# Output.net
KiCad netlist of a schematic drawn in Altium Designer
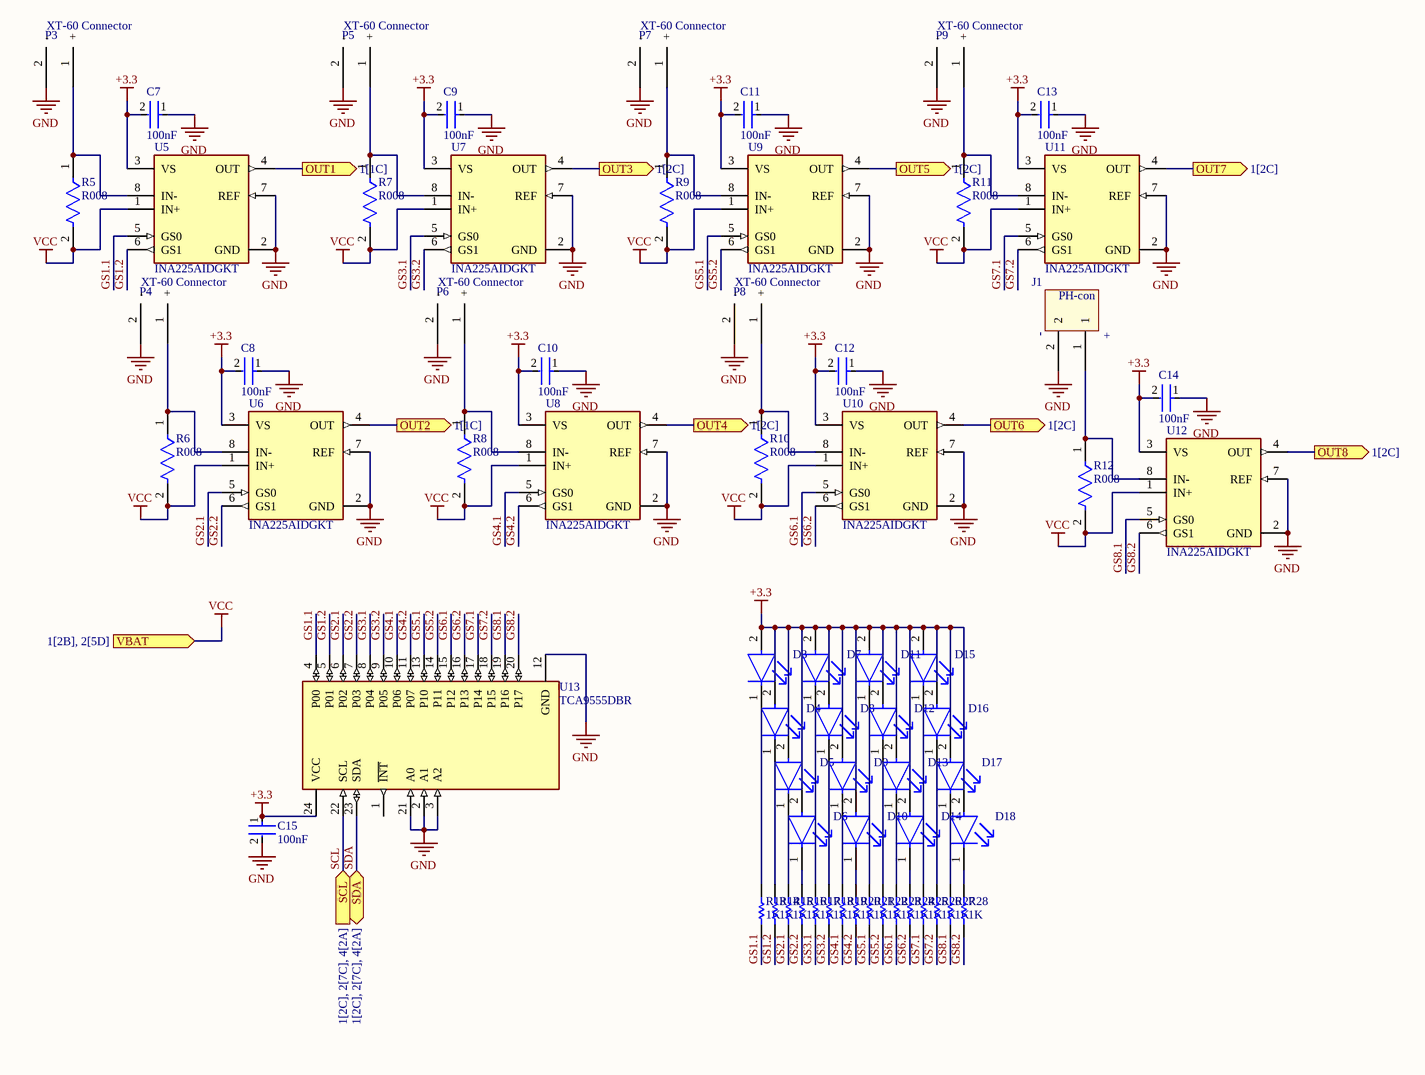
[diagram p0: Output.SchDoc]

(export (version "E")
  (design (tool "Eeschema 10.0.6"))
  (components
    (comp (ref "C7")
      (value "100nF")
      (footprint "FP-0805-L_2_01_0_2-W_1_25-IPC_B")
      (description "General Purpose Ceramic Capacitor, 0805, 100nF, 10%, X7R, 15%, 100V")
      (fields (field (name "VOLTAGE") "100V") (field (name "TOLERANCE") "10%"))
      (libsource (lib "Altium Content Vault") (part "b4654b650e69147ec39a6b967a45e02"))
    )
    (comp (ref "C8")
      (value "100nF")
      (footprint "FP-0805-L_2_01_0_2-W_1_25-IPC_B")
      (description "General Purpose Ceramic Capacitor, 0805, 100nF, 10%, X7R, 15%, 100V")
      (fields (field (name "VOLTAGE") "100V") (field (name "TOLERANCE") "10%"))
      (libsource (lib "Altium Content Vault") (part "b4654b650e69147ec39a6b967a45e02"))
    )
    (comp (ref "C9")
      (value "100nF")
      (footprint "FP-0805-L_2_01_0_2-W_1_25-IPC_B")
      (description "General Purpose Ceramic Capacitor, 0805, 100nF, 10%, X7R, 15%, 100V")
      (fields (field (name "VOLTAGE") "100V") (field (name "TOLERANCE") "10%"))
      (libsource (lib "Altium Content Vault") (part "b4654b650e69147ec39a6b967a45e02"))
    )
    (comp (ref "C10")
      (value "100nF")
      (footprint "FP-0805-L_2_01_0_2-W_1_25-IPC_B")
      (description "General Purpose Ceramic Capacitor, 0805, 100nF, 10%, X7R, 15%, 100V")
      (fields (field (name "VOLTAGE") "100V") (field (name "TOLERANCE") "10%"))
      (libsource (lib "Altium Content Vault") (part "b4654b650e69147ec39a6b967a45e02"))
    )
    (comp (ref "C11")
      (value "100nF")
      (footprint "FP-0805-L_2_01_0_2-W_1_25-IPC_B")
      (description "General Purpose Ceramic Capacitor, 0805, 100nF, 10%, X7R, 15%, 100V")
      (fields (field (name "VOLTAGE") "100V") (field (name "TOLERANCE") "10%"))
      (libsource (lib "Altium Content Vault") (part "b4654b650e69147ec39a6b967a45e02"))
    )
    (comp (ref "C12")
      (value "100nF")
      (footprint "FP-0805-L_2_01_0_2-W_1_25-IPC_B")
      (description "General Purpose Ceramic Capacitor, 0805, 100nF, 10%, X7R, 15%, 100V")
      (fields (field (name "VOLTAGE") "100V") (field (name "TOLERANCE") "10%"))
      (libsource (lib "Altium Content Vault") (part "b4654b650e69147ec39a6b967a45e02"))
    )
    (comp (ref "C13")
      (value "100nF")
      (footprint "FP-0805-L_2_01_0_2-W_1_25-IPC_B")
      (description "General Purpose Ceramic Capacitor, 0805, 100nF, 10%, X7R, 15%, 100V")
      (fields (field (name "VOLTAGE") "100V") (field (name "TOLERANCE") "10%"))
      (libsource (lib "Altium Content Vault") (part "b4654b650e69147ec39a6b967a45e02"))
    )
    (comp (ref "C14")
      (value "100nF")
      (footprint "FP-0805-L_2_01_0_2-W_1_25-IPC_B")
      (description "General Purpose Ceramic Capacitor, 0805, 100nF, 10%, X7R, 15%, 100V")
      (fields (field (name "VOLTAGE") "100V") (field (name "TOLERANCE") "10%"))
      (libsource (lib "Altium Content Vault") (part "b4654b650e69147ec39a6b967a45e02"))
    )
    (comp (ref "C15")
      (value "100nF")
      (footprint "FP-0805-L_2_01_0_2-W_1_25-IPC_B")
      (description "General Purpose Ceramic Capacitor, 0805, 100nF, 10%, X7R, 15%, 100V")
      (fields (field (name "VOLTAGE") "100V") (field (name "TOLERANCE") "10%"))
      (libsource (lib "Altium Content Vault") (part "b4654b650e69147ec39a6b967a45e02"))
    )
    (comp (ref "D3")
      (value "TLLG4401")
      (footprint "FP-6_544-5255_01-4-MFG")
      (description "TLLG4401 LED, Green, 2mcd, 3mmDia., T-1, +/-25deg, 565nm, 7mA, 1.9V Vf, 20V Vr, 20mW, -40")
      (libsource (lib "Altium Content Vault") (part "8706943c75ba83719d021d2fdc84c58"))
    )
    (comp (ref "D4")
      (value "TLLG4401")
      (footprint "FP-6_544-5255_01-4-MFG")
      (description "TLLG4401 LED, Green, 2mcd, 3mmDia., T-1, +/-25deg, 565nm, 7mA, 1.9V Vf, 20V Vr, 20mW, -40")
      (libsource (lib "Altium Content Vault") (part "8706943c75ba83719d021d2fdc84c58"))
    )
    (comp (ref "D5")
      (value "TLLG4401")
      (footprint "FP-6_544-5255_01-4-MFG")
      (description "TLLG4401 LED, Green, 2mcd, 3mmDia., T-1, +/-25deg, 565nm, 7mA, 1.9V Vf, 20V Vr, 20mW, -40")
      (libsource (lib "Altium Content Vault") (part "8706943c75ba83719d021d2fdc84c58"))
    )
    (comp (ref "D6")
      (value "TLLG4401")
      (footprint "FP-6_544-5255_01-4-MFG")
      (description "TLLG4401 LED, Green, 2mcd, 3mmDia., T-1, +/-25deg, 565nm, 7mA, 1.9V Vf, 20V Vr, 20mW, -40")
      (libsource (lib "Altium Content Vault") (part "8706943c75ba83719d021d2fdc84c58"))
    )
    (comp (ref "D7")
      (value "TLLG4401")
      (footprint "FP-6_544-5255_01-4-MFG")
      (description "TLLG4401 LED, Green, 2mcd, 3mmDia., T-1, +/-25deg, 565nm, 7mA, 1.9V Vf, 20V Vr, 20mW, -40")
      (libsource (lib "Altium Content Vault") (part "8706943c75ba83719d021d2fdc84c58"))
    )
    (comp (ref "D8")
      (value "TLLG4401")
      (footprint "FP-6_544-5255_01-4-MFG")
      (description "TLLG4401 LED, Green, 2mcd, 3mmDia., T-1, +/-25deg, 565nm, 7mA, 1.9V Vf, 20V Vr, 20mW, -40")
      (libsource (lib "Altium Content Vault") (part "8706943c75ba83719d021d2fdc84c58"))
    )
    (comp (ref "D9")
      (value "TLLG4401")
      (footprint "FP-6_544-5255_01-4-MFG")
      (description "TLLG4401 LED, Green, 2mcd, 3mmDia., T-1, +/-25deg, 565nm, 7mA, 1.9V Vf, 20V Vr, 20mW, -40")
      (libsource (lib "Altium Content Vault") (part "8706943c75ba83719d021d2fdc84c58"))
    )
    (comp (ref "D10")
      (value "TLLG4401")
      (footprint "FP-6_544-5255_01-4-MFG")
      (description "TLLG4401 LED, Green, 2mcd, 3mmDia., T-1, +/-25deg, 565nm, 7mA, 1.9V Vf, 20V Vr, 20mW, -40")
      (libsource (lib "Altium Content Vault") (part "8706943c75ba83719d021d2fdc84c58"))
    )
    (comp (ref "D11")
      (value "TLLG4401")
      (footprint "FP-6_544-5255_01-4-MFG")
      (description "TLLG4401 LED, Green, 2mcd, 3mmDia., T-1, +/-25deg, 565nm, 7mA, 1.9V Vf, 20V Vr, 20mW, -40")
      (libsource (lib "Altium Content Vault") (part "8706943c75ba83719d021d2fdc84c58"))
    )
    (comp (ref "D12")
      (value "TLLG4401")
      (footprint "FP-6_544-5255_01-4-MFG")
      (description "TLLG4401 LED, Green, 2mcd, 3mmDia., T-1, +/-25deg, 565nm, 7mA, 1.9V Vf, 20V Vr, 20mW, -40")
      (libsource (lib "Altium Content Vault") (part "8706943c75ba83719d021d2fdc84c58"))
    )
    (comp (ref "D13")
      (value "TLLG4401")
      (footprint "FP-6_544-5255_01-4-MFG")
      (description "TLLG4401 LED, Green, 2mcd, 3mmDia., T-1, +/-25deg, 565nm, 7mA, 1.9V Vf, 20V Vr, 20mW, -40")
      (libsource (lib "Altium Content Vault") (part "8706943c75ba83719d021d2fdc84c58"))
    )
    (comp (ref "D14")
      (value "TLLG4401")
      (footprint "FP-6_544-5255_01-4-MFG")
      (description "TLLG4401 LED, Green, 2mcd, 3mmDia., T-1, +/-25deg, 565nm, 7mA, 1.9V Vf, 20V Vr, 20mW, -40")
      (libsource (lib "Altium Content Vault") (part "8706943c75ba83719d021d2fdc84c58"))
    )
    (comp (ref "D15")
      (value "TLLG4401")
      (footprint "FP-6_544-5255_01-4-MFG")
      (description "TLLG4401 LED, Green, 2mcd, 3mmDia., T-1, +/-25deg, 565nm, 7mA, 1.9V Vf, 20V Vr, 20mW, -40")
      (libsource (lib "Altium Content Vault") (part "8706943c75ba83719d021d2fdc84c58"))
    )
    (comp (ref "D16")
      (value "TLLG4401")
      (footprint "FP-6_544-5255_01-4-MFG")
      (description "TLLG4401 LED, Green, 2mcd, 3mmDia., T-1, +/-25deg, 565nm, 7mA, 1.9V Vf, 20V Vr, 20mW, -40")
      (libsource (lib "Altium Content Vault") (part "8706943c75ba83719d021d2fdc84c58"))
    )
    (comp (ref "D17")
      (value "TLLG4401")
      (footprint "FP-6_544-5255_01-4-MFG")
      (description "TLLG4401 LED, Green, 2mcd, 3mmDia., T-1, +/-25deg, 565nm, 7mA, 1.9V Vf, 20V Vr, 20mW, -40")
      (libsource (lib "Altium Content Vault") (part "8706943c75ba83719d021d2fdc84c58"))
    )
    (comp (ref "D18")
      (value "TLLG4401")
      (footprint "FP-6_544-5255_01-4-MFG")
      (description "TLLG4401 LED, Green, 2mcd, 3mmDia., T-1, +/-25deg, 565nm, 7mA, 1.9V Vf, 20V Vr, 20mW, -40")
      (libsource (lib "Altium Content Vault") (part "8706943c75ba83719d021d2fdc84c58"))
    )
    (comp (ref "J1")
      (value "PH-con")
      (footprint "Phoenix")
      (libsource (lib "XT+PHOENIX") (part "Connector_2"))
    )
    (comp (ref "P3")
      (value "XT-60 Connector")
      (footprint "2")
      (fields
        (field (name "MANUFACTURER") "POLOLU")
        (field (name "MANUFACTURER PART NUMBER") "XT60 YELLOW")
        (field (name "SUPPLIER PART NUMBER 1") "XT-60 Connector")
      )
      (libsource (lib "AltiumLibraryDDT") (part "XT-60 Connector"))
    )
    (comp (ref "P4")
      (value "XT-60 Connector")
      (footprint "2")
      (fields
        (field (name "MANUFACTURER") "POLOLU")
        (field (name "MANUFACTURER PART NUMBER") "XT60 YELLOW")
        (field (name "SUPPLIER PART NUMBER 1") "XT-60 Connector")
      )
      (libsource (lib "AltiumLibraryDDT") (part "XT-60 Connector"))
    )
    (comp (ref "P5")
      (value "XT-60 Connector")
      (footprint "2")
      (fields
        (field (name "MANUFACTURER") "POLOLU")
        (field (name "MANUFACTURER PART NUMBER") "XT60 YELLOW")
        (field (name "SUPPLIER PART NUMBER 1") "XT-60 Connector")
      )
      (libsource (lib "AltiumLibraryDDT") (part "XT-60 Connector"))
    )
    (comp (ref "P6")
      (value "XT-60 Connector")
      (footprint "2")
      (fields
        (field (name "MANUFACTURER") "POLOLU")
        (field (name "MANUFACTURER PART NUMBER") "XT60 YELLOW")
        (field (name "SUPPLIER PART NUMBER 1") "XT-60 Connector")
      )
      (libsource (lib "AltiumLibraryDDT") (part "XT-60 Connector"))
    )
    (comp (ref "P7")
      (value "XT-60 Connector")
      (footprint "2")
      (fields
        (field (name "MANUFACTURER") "POLOLU")
        (field (name "MANUFACTURER PART NUMBER") "XT60 YELLOW")
        (field (name "SUPPLIER PART NUMBER 1") "XT-60 Connector")
      )
      (libsource (lib "AltiumLibraryDDT") (part "XT-60 Connector"))
    )
    (comp (ref "P8")
      (value "XT-60 Connector")
      (footprint "2")
      (fields
        (field (name "MANUFACTURER") "POLOLU")
        (field (name "MANUFACTURER PART NUMBER") "XT60 YELLOW")
        (field (name "SUPPLIER PART NUMBER 1") "XT-60 Connector")
      )
      (libsource (lib "AltiumLibraryDDT") (part "XT-60 Connector"))
    )
    (comp (ref "P9")
      (value "XT-60 Connector")
      (footprint "2")
      (fields
        (field (name "MANUFACTURER") "POLOLU")
        (field (name "MANUFACTURER PART NUMBER") "XT60 YELLOW")
        (field (name "SUPPLIER PART NUMBER 1") "XT-60 Connector")
      )
      (libsource (lib "AltiumLibraryDDT") (part "XT-60 Connector"))
    )
    (comp (ref "R5")
      (value "R008")
      (footprint "FP-RL2512-MFG")
      (description "RES 0.1 OHM 1% 1W 2512")
      (fields
        (field (name "OCTOPART") "https://octopart.com/rl2512fk-070r1l-yageo-42334369")
        (field (name "MANUFACTURER") "YAGEO")
      )
      (libsource (lib "Altium Content Vault") (part "1029c3af85768c4190bb7ad29bc67b5"))
    )
    (comp (ref "R6")
      (value "R008")
      (footprint "FP-RL2512-MFG")
      (description "RES 0.1 OHM 1% 1W 2512")
      (fields
        (field (name "OCTOPART") "https://octopart.com/rl2512fk-070r1l-yageo-42334369")
        (field (name "MANUFACTURER") "YAGEO")
      )
      (libsource (lib "Altium Content Vault") (part "1029c3af85768c4190bb7ad29bc67b5"))
    )
    (comp (ref "R7")
      (value "R008")
      (footprint "FP-RL2512-MFG")
      (description "RES 0.1 OHM 1% 1W 2512")
      (fields
        (field (name "OCTOPART") "https://octopart.com/rl2512fk-070r1l-yageo-42334369")
        (field (name "MANUFACTURER") "YAGEO")
      )
      (libsource (lib "Altium Content Vault") (part "1029c3af85768c4190bb7ad29bc67b5"))
    )
    (comp (ref "R8")
      (value "R008")
      (footprint "FP-RL2512-MFG")
      (description "RES 0.1 OHM 1% 1W 2512")
      (fields
        (field (name "OCTOPART") "https://octopart.com/rl2512fk-070r1l-yageo-42334369")
        (field (name "MANUFACTURER") "YAGEO")
      )
      (libsource (lib "Altium Content Vault") (part "1029c3af85768c4190bb7ad29bc67b5"))
    )
    (comp (ref "R9")
      (value "R008")
      (footprint "FP-RL2512-MFG")
      (description "RES 0.1 OHM 1% 1W 2512")
      (fields
        (field (name "OCTOPART") "https://octopart.com/rl2512fk-070r1l-yageo-42334369")
        (field (name "MANUFACTURER") "YAGEO")
      )
      (libsource (lib "Altium Content Vault") (part "1029c3af85768c4190bb7ad29bc67b5"))
    )
    (comp (ref "R10")
      (value "R008")
      (footprint "FP-RL2512-MFG")
      (description "RES 0.1 OHM 1% 1W 2512")
      (fields
        (field (name "OCTOPART") "https://octopart.com/rl2512fk-070r1l-yageo-42334369")
        (field (name "MANUFACTURER") "YAGEO")
      )
      (libsource (lib "Altium Content Vault") (part "1029c3af85768c4190bb7ad29bc67b5"))
    )
    (comp (ref "R11")
      (value "R008")
      (footprint "FP-RL2512-MFG")
      (description "RES 0.1 OHM 1% 1W 2512")
      (fields
        (field (name "OCTOPART") "https://octopart.com/rl2512fk-070r1l-yageo-42334369")
        (field (name "MANUFACTURER") "YAGEO")
      )
      (libsource (lib "Altium Content Vault") (part "1029c3af85768c4190bb7ad29bc67b5"))
    )
    (comp (ref "R12")
      (value "R008")
      (footprint "FP-RL2512-MFG")
      (description "RES 0.1 OHM 1% 1W 2512")
      (fields
        (field (name "OCTOPART") "https://octopart.com/rl2512fk-070r1l-yageo-42334369")
        (field (name "MANUFACTURER") "YAGEO")
      )
      (libsource (lib "Altium Content Vault") (part "1029c3af85768c4190bb7ad29bc67b5"))
    )
    (comp (ref "R13")
      (value "1K")
      (footprint "RESC2013X60X35ML10T20")
      (description "Chip Resistor, 1 KOhm, +/- 1%, 125 mW, -55 to 155 degC, 0805 (2012 Metric), RoHS, Tape and Reel")
      (fields (field (name "TOLERANCE") "1%") (field (name "MANUFACTURER") "Yageo"))
      (libsource (lib "Altium Content Vault") (part "RES-2"))
    )
    (comp (ref "R14")
      (value "1K")
      (footprint "RESC2013X60X35ML10T20")
      (description "Chip Resistor, 1 KOhm, +/- 1%, 125 mW, -55 to 155 degC, 0805 (2012 Metric), RoHS, Tape and Reel")
      (fields (field (name "TOLERANCE") "1%") (field (name "MANUFACTURER") "Yageo"))
      (libsource (lib "Altium Content Vault") (part "RES-2"))
    )
    (comp (ref "R15")
      (value "1K")
      (footprint "RESC2013X60X35ML10T20")
      (description "Chip Resistor, 1 KOhm, +/- 1%, 125 mW, -55 to 155 degC, 0805 (2012 Metric), RoHS, Tape and Reel")
      (fields (field (name "TOLERANCE") "1%") (field (name "MANUFACTURER") "Yageo"))
      (libsource (lib "Altium Content Vault") (part "RES-2"))
    )
    (comp (ref "R16")
      (value "1K")
      (footprint "RESC2013X60X35ML10T20")
      (description "Chip Resistor, 1 KOhm, +/- 1%, 125 mW, -55 to 155 degC, 0805 (2012 Metric), RoHS, Tape and Reel")
      (fields (field (name "TOLERANCE") "1%") (field (name "MANUFACTURER") "Yageo"))
      (libsource (lib "Altium Content Vault") (part "RES-2"))
    )
    (comp (ref "R17")
      (value "1K")
      (footprint "RESC2013X60X35ML10T20")
      (description "Chip Resistor, 1 KOhm, +/- 1%, 125 mW, -55 to 155 degC, 0805 (2012 Metric), RoHS, Tape and Reel")
      (fields (field (name "TOLERANCE") "1%") (field (name "MANUFACTURER") "Yageo"))
      (libsource (lib "Altium Content Vault") (part "RES-2"))
    )
    (comp (ref "R18")
      (value "1K")
      (footprint "RESC2013X60X35ML10T20")
      (description "Chip Resistor, 1 KOhm, +/- 1%, 125 mW, -55 to 155 degC, 0805 (2012 Metric), RoHS, Tape and Reel")
      (fields (field (name "TOLERANCE") "1%") (field (name "MANUFACTURER") "Yageo"))
      (libsource (lib "Altium Content Vault") (part "RES-2"))
    )
    (comp (ref "R19")
      (value "1K")
      (footprint "RESC2013X60X35ML10T20")
      (description "Chip Resistor, 1 KOhm, +/- 1%, 125 mW, -55 to 155 degC, 0805 (2012 Metric), RoHS, Tape and Reel")
      (fields (field (name "TOLERANCE") "1%") (field (name "MANUFACTURER") "Yageo"))
      (libsource (lib "Altium Content Vault") (part "RES-2"))
    )
    (comp (ref "R20")
      (value "1K")
      (footprint "RESC2013X60X35ML10T20")
      (description "Chip Resistor, 1 KOhm, +/- 1%, 125 mW, -55 to 155 degC, 0805 (2012 Metric), RoHS, Tape and Reel")
      (fields (field (name "TOLERANCE") "1%") (field (name "MANUFACTURER") "Yageo"))
      (libsource (lib "Altium Content Vault") (part "RES-2"))
    )
    (comp (ref "R21")
      (value "1K")
      (footprint "RESC2013X60X35ML10T20")
      (description "Chip Resistor, 1 KOhm, +/- 1%, 125 mW, -55 to 155 degC, 0805 (2012 Metric), RoHS, Tape and Reel")
      (fields (field (name "TOLERANCE") "1%") (field (name "MANUFACTURER") "Yageo"))
      (libsource (lib "Altium Content Vault") (part "RES-2"))
    )
    (comp (ref "R22")
      (value "1K")
      (footprint "RESC2013X60X35ML10T20")
      (description "Chip Resistor, 1 KOhm, +/- 1%, 125 mW, -55 to 155 degC, 0805 (2012 Metric), RoHS, Tape and Reel")
      (fields (field (name "TOLERANCE") "1%") (field (name "MANUFACTURER") "Yageo"))
      (libsource (lib "Altium Content Vault") (part "RES-2"))
    )
    (comp (ref "R23")
      (value "1K")
      (footprint "RESC2013X60X35ML10T20")
      (description "Chip Resistor, 1 KOhm, +/- 1%, 125 mW, -55 to 155 degC, 0805 (2012 Metric), RoHS, Tape and Reel")
      (fields (field (name "TOLERANCE") "1%") (field (name "MANUFACTURER") "Yageo"))
      (libsource (lib "Altium Content Vault") (part "RES-2"))
    )
    (comp (ref "R24")
      (value "1K")
      (footprint "RESC2013X60X35ML10T20")
      (description "Chip Resistor, 1 KOhm, +/- 1%, 125 mW, -55 to 155 degC, 0805 (2012 Metric), RoHS, Tape and Reel")
      (fields (field (name "TOLERANCE") "1%") (field (name "MANUFACTURER") "Yageo"))
      (libsource (lib "Altium Content Vault") (part "RES-2"))
    )
    (comp (ref "R25")
      (value "1K")
      (footprint "RESC2013X60X35ML10T20")
      (description "Chip Resistor, 1 KOhm, +/- 1%, 125 mW, -55 to 155 degC, 0805 (2012 Metric), RoHS, Tape and Reel")
      (fields (field (name "TOLERANCE") "1%") (field (name "MANUFACTURER") "Yageo"))
      (libsource (lib "Altium Content Vault") (part "RES-2"))
    )
    (comp (ref "R26")
      (value "1K")
      (footprint "RESC2013X60X35ML10T20")
      (description "Chip Resistor, 1 KOhm, +/- 1%, 125 mW, -55 to 155 degC, 0805 (2012 Metric), RoHS, Tape and Reel")
      (fields (field (name "TOLERANCE") "1%") (field (name "MANUFACTURER") "Yageo"))
      (libsource (lib "Altium Content Vault") (part "RES-2"))
    )
    (comp (ref "R27")
      (value "1K")
      (footprint "RESC2013X60X35ML10T20")
      (description "Chip Resistor, 1 KOhm, +/- 1%, 125 mW, -55 to 155 degC, 0805 (2012 Metric), RoHS, Tape and Reel")
      (fields (field (name "TOLERANCE") "1%") (field (name "MANUFACTURER") "Yageo"))
      (libsource (lib "Altium Content Vault") (part "RES-2"))
    )
    (comp (ref "R28")
      (value "1K")
      (footprint "RESC2013X60X35ML10T20")
      (description "Chip Resistor, 1 KOhm, +/- 1%, 125 mW, -55 to 155 degC, 0805 (2012 Metric), RoHS, Tape and Reel")
      (fields (field (name "TOLERANCE") "1%") (field (name "MANUFACTURER") "Yageo"))
      (libsource (lib "Altium Content Vault") (part "RES-2"))
    )
    (comp (ref "U5")
      (value "INA225AIDGKT")
      (footprint "FP-INA225AIDGKT-IPC_A")
      (description "IC MONITOR PWR/CUR BIDIR 8VSSOP")
      (fields
        (field (name "OCTOPART") "https://octopart.com/ina225aidgkt-texas+instruments-28946314")
        (field (name "MANUFACTURER") "Texas Instruments")
      )
      (libsource (lib "Altium Content Vault") (part "c359911d667b8e4eb68c8ff16fe5c28"))
    )
    (comp (ref "U6")
      (value "INA225AIDGKT")
      (footprint "FP-INA225AIDGKT-IPC_A")
      (description "IC MONITOR PWR/CUR BIDIR 8VSSOP")
      (fields
        (field (name "OCTOPART") "https://octopart.com/ina225aidgkt-texas+instruments-28946314")
        (field (name "MANUFACTURER") "Texas Instruments")
      )
      (libsource (lib "Altium Content Vault") (part "c359911d667b8e4eb68c8ff16fe5c28"))
    )
    (comp (ref "U7")
      (value "INA225AIDGKT")
      (footprint "FP-INA225AIDGKT-IPC_A")
      (description "IC MONITOR PWR/CUR BIDIR 8VSSOP")
      (fields
        (field (name "OCTOPART") "https://octopart.com/ina225aidgkt-texas+instruments-28946314")
        (field (name "MANUFACTURER") "Texas Instruments")
      )
      (libsource (lib "Altium Content Vault") (part "c359911d667b8e4eb68c8ff16fe5c28"))
    )
    (comp (ref "U8")
      (value "INA225AIDGKT")
      (footprint "FP-INA225AIDGKT-IPC_A")
      (description "IC MONITOR PWR/CUR BIDIR 8VSSOP")
      (fields
        (field (name "OCTOPART") "https://octopart.com/ina225aidgkt-texas+instruments-28946314")
        (field (name "MANUFACTURER") "Texas Instruments")
      )
      (libsource (lib "Altium Content Vault") (part "c359911d667b8e4eb68c8ff16fe5c28"))
    )
    (comp (ref "U9")
      (value "INA225AIDGKT")
      (footprint "FP-INA225AIDGKT-IPC_A")
      (description "IC MONITOR PWR/CUR BIDIR 8VSSOP")
      (fields
        (field (name "OCTOPART") "https://octopart.com/ina225aidgkt-texas+instruments-28946314")
        (field (name "MANUFACTURER") "Texas Instruments")
      )
      (libsource (lib "Altium Content Vault") (part "c359911d667b8e4eb68c8ff16fe5c28"))
    )
    (comp (ref "U10")
      (value "INA225AIDGKT")
      (footprint "FP-INA225AIDGKT-IPC_A")
      (description "IC MONITOR PWR/CUR BIDIR 8VSSOP")
      (fields
        (field (name "OCTOPART") "https://octopart.com/ina225aidgkt-texas+instruments-28946314")
        (field (name "MANUFACTURER") "Texas Instruments")
      )
      (libsource (lib "Altium Content Vault") (part "c359911d667b8e4eb68c8ff16fe5c28"))
    )
    (comp (ref "U11")
      (value "INA225AIDGKT")
      (footprint "FP-INA225AIDGKT-IPC_A")
      (description "IC MONITOR PWR/CUR BIDIR 8VSSOP")
      (fields
        (field (name "OCTOPART") "https://octopart.com/ina225aidgkt-texas+instruments-28946314")
        (field (name "MANUFACTURER") "Texas Instruments")
      )
      (libsource (lib "Altium Content Vault") (part "c359911d667b8e4eb68c8ff16fe5c28"))
    )
    (comp (ref "U12")
      (value "INA225AIDGKT")
      (footprint "FP-INA225AIDGKT-IPC_A")
      (description "IC MONITOR PWR/CUR BIDIR 8VSSOP")
      (fields
        (field (name "OCTOPART") "https://octopart.com/ina225aidgkt-texas+instruments-28946314")
        (field (name "MANUFACTURER") "Texas Instruments")
      )
      (libsource (lib "Altium Content Vault") (part "c359911d667b8e4eb68c8ff16fe5c28"))
    )
    (comp (ref "U13")
      (value "TCA9555DBR")
      (footprint "FP-DB0024A-IPC_A")
      (description "IC I/O EXPANDER 16B 24SSOP")
      (libsource (lib "Altium Content Vault") (part "d0eb17f36d141fc89679fdc1217173a"))
    )
  )
  (nets
    (net (code "1") (name "+3.3") (class "Default")
      (node (ref "C10") (pin "2") (pinfunction "2_2") (pintype "passive"))
      (node (ref "C11") (pin "2") (pinfunction "2_2") (pintype "passive"))
      (node (ref "C12") (pin "2") (pinfunction "2_2") (pintype "passive"))
      (node (ref "C13") (pin "2") (pinfunction "2_2") (pintype "passive"))
      (node (ref "C14") (pin "2") (pinfunction "2_2") (pintype "passive"))
      (node (ref "C15") (pin "1") (pinfunction "1_1") (pintype "passive"))
      (node (ref "C7") (pin "2") (pinfunction "2_2") (pintype "passive"))
      (node (ref "C8") (pin "2") (pinfunction "2_2") (pintype "passive"))
      (node (ref "C9") (pin "2") (pinfunction "2_2") (pintype "passive"))
      (node (ref "D10") (pin "2") (pinfunction "A_2") (pintype "passive"))
      (node (ref "D11") (pin "2") (pinfunction "A_2") (pintype "passive"))
      (node (ref "D12") (pin "2") (pinfunction "A_2") (pintype "passive"))
      (node (ref "D13") (pin "2") (pinfunction "A_2") (pintype "passive"))
      (node (ref "D14") (pin "2") (pinfunction "A_2") (pintype "passive"))
      (node (ref "D15") (pin "2") (pinfunction "A_2") (pintype "passive"))
      (node (ref "D16") (pin "2") (pinfunction "A_2") (pintype "passive"))
      (node (ref "D17") (pin "2") (pinfunction "A_2") (pintype "passive"))
      (node (ref "D18") (pin "2") (pinfunction "A_2") (pintype "passive"))
      (node (ref "D3") (pin "2") (pinfunction "A_2") (pintype "passive"))
      (node (ref "D4") (pin "2") (pinfunction "A_2") (pintype "passive"))
      (node (ref "D5") (pin "2") (pinfunction "A_2") (pintype "passive"))
      (node (ref "D6") (pin "2") (pinfunction "A_2") (pintype "passive"))
      (node (ref "D7") (pin "2") (pinfunction "A_2") (pintype "passive"))
      (node (ref "D8") (pin "2") (pinfunction "A_2") (pintype "passive"))
      (node (ref "D9") (pin "2") (pinfunction "A_2") (pintype "passive"))
      (node (ref "U10") (pin "3") (pinfunction "VS_3") (pintype "power_in"))
      (node (ref "U11") (pin "3") (pinfunction "VS_3") (pintype "power_in"))
      (node (ref "U12") (pin "3") (pinfunction "VS_3") (pintype "power_in"))
      (node (ref "U13") (pin "24") (pinfunction "VCC_24") (pintype "power_in"))
      (node (ref "U5") (pin "3") (pinfunction "VS_3") (pintype "power_in"))
      (node (ref "U6") (pin "3") (pinfunction "VS_3") (pintype "power_in"))
      (node (ref "U7") (pin "3") (pinfunction "VS_3") (pintype "power_in"))
      (node (ref "U8") (pin "3") (pinfunction "VS_3") (pintype "power_in"))
      (node (ref "U9") (pin "3") (pinfunction "VS_3") (pintype "power_in"))
    )
    (net (code "2") (name "/GS1.1") (class "Default")
      (node (ref "R13") (pin "1") (pinfunction "1_1") (pintype "passive"))
      (node (ref "U13") (pin "4") (pinfunction "P00_4") (pintype "bidirectional"))
      (node (ref "U5") (pin "5") (pinfunction "GS0_5") (pintype "input"))
    )
    (net (code "3") (name "/GS1.2") (class "Default")
      (node (ref "R14") (pin "1") (pinfunction "1_1") (pintype "passive"))
      (node (ref "U13") (pin "5") (pinfunction "P01_5") (pintype "bidirectional"))
      (node (ref "U5") (pin "6") (pinfunction "GS1_6") (pintype "output"))
    )
    (net (code "4") (name "/GS2.1") (class "Default")
      (node (ref "R15") (pin "1") (pinfunction "1_1") (pintype "passive"))
      (node (ref "U13") (pin "6") (pinfunction "P02_6") (pintype "bidirectional"))
      (node (ref "U6") (pin "5") (pinfunction "GS0_5") (pintype "input"))
    )
    (net (code "5") (name "/GS2.2") (class "Default")
      (node (ref "R16") (pin "1") (pinfunction "1_1") (pintype "passive"))
      (node (ref "U13") (pin "7") (pinfunction "P03_7") (pintype "bidirectional"))
      (node (ref "U6") (pin "6") (pinfunction "GS1_6") (pintype "output"))
    )
    (net (code "6") (name "/GS3.1") (class "Default")
      (node (ref "R17") (pin "1") (pinfunction "1_1") (pintype "passive"))
      (node (ref "U13") (pin "8") (pinfunction "P04_8") (pintype "bidirectional"))
      (node (ref "U7") (pin "5") (pinfunction "GS0_5") (pintype "input"))
    )
    (net (code "7") (name "/GS3.2") (class "Default")
      (node (ref "R18") (pin "1") (pinfunction "1_1") (pintype "passive"))
      (node (ref "U13") (pin "9") (pinfunction "P05_9") (pintype "bidirectional"))
      (node (ref "U7") (pin "6") (pinfunction "GS1_6") (pintype "output"))
    )
    (net (code "8") (name "/GS4.1") (class "Default")
      (node (ref "R19") (pin "1") (pinfunction "1_1") (pintype "passive"))
      (node (ref "U13") (pin "10") (pinfunction "P06_10") (pintype "bidirectional"))
      (node (ref "U8") (pin "5") (pinfunction "GS0_5") (pintype "input"))
    )
    (net (code "9") (name "/GS4.2") (class "Default")
      (node (ref "R20") (pin "1") (pinfunction "1_1") (pintype "passive"))
      (node (ref "U13") (pin "11") (pinfunction "P07_11") (pintype "bidirectional"))
      (node (ref "U8") (pin "6") (pinfunction "GS1_6") (pintype "output"))
    )
    (net (code "10") (name "/GS5.1") (class "Default")
      (node (ref "R21") (pin "1") (pinfunction "1_1") (pintype "passive"))
      (node (ref "U13") (pin "13") (pinfunction "P10_13") (pintype "bidirectional"))
      (node (ref "U9") (pin "5") (pinfunction "GS0_5") (pintype "input"))
    )
    (net (code "11") (name "/GS5.2") (class "Default")
      (node (ref "R22") (pin "1") (pinfunction "1_1") (pintype "passive"))
      (node (ref "U13") (pin "14") (pinfunction "P11_14") (pintype "bidirectional"))
      (node (ref "U9") (pin "6") (pinfunction "GS1_6") (pintype "output"))
    )
    (net (code "12") (name "/GS6.1") (class "Default")
      (node (ref "R23") (pin "1") (pinfunction "1_1") (pintype "passive"))
      (node (ref "U10") (pin "5") (pinfunction "GS0_5") (pintype "input"))
      (node (ref "U13") (pin "15") (pinfunction "P12_15") (pintype "bidirectional"))
    )
    (net (code "13") (name "/GS6.2") (class "Default")
      (node (ref "R24") (pin "1") (pinfunction "1_1") (pintype "passive"))
      (node (ref "U10") (pin "6") (pinfunction "GS1_6") (pintype "output"))
      (node (ref "U13") (pin "16") (pinfunction "P13_16") (pintype "bidirectional"))
    )
    (net (code "14") (name "/GS7.1") (class "Default")
      (node (ref "R25") (pin "1") (pinfunction "1_1") (pintype "passive"))
      (node (ref "U11") (pin "5") (pinfunction "GS0_5") (pintype "input"))
      (node (ref "U13") (pin "17") (pinfunction "P14_17") (pintype "bidirectional"))
    )
    (net (code "15") (name "/GS7.2") (class "Default")
      (node (ref "R26") (pin "1") (pinfunction "1_1") (pintype "passive"))
      (node (ref "U11") (pin "6") (pinfunction "GS1_6") (pintype "output"))
      (node (ref "U13") (pin "18") (pinfunction "P15_18") (pintype "bidirectional"))
    )
    (net (code "16") (name "/GS8.1") (class "Default")
      (node (ref "R27") (pin "1") (pinfunction "1_1") (pintype "passive"))
      (node (ref "U12") (pin "5") (pinfunction "GS0_5") (pintype "input"))
      (node (ref "U13") (pin "19") (pinfunction "P16_19") (pintype "bidirectional"))
    )
    (net (code "17") (name "/GS8.2") (class "Default")
      (node (ref "R28") (pin "1") (pinfunction "1_1") (pintype "passive"))
      (node (ref "U12") (pin "6") (pinfunction "GS1_6") (pintype "output"))
      (node (ref "U13") (pin "20") (pinfunction "P17_20") (pintype "bidirectional"))
    )
    (net (code "18") (name "/OUT1") (class "Default")
      (node (ref "U5") (pin "4") (pinfunction "OUT_4") (pintype "output"))
    )
    (net (code "19") (name "/OUT2") (class "Default")
      (node (ref "U6") (pin "4") (pinfunction "OUT_4") (pintype "output"))
    )
    (net (code "20") (name "/OUT3") (class "Default")
      (node (ref "U7") (pin "4") (pinfunction "OUT_4") (pintype "output"))
    )
    (net (code "21") (name "/OUT4") (class "Default")
      (node (ref "U8") (pin "4") (pinfunction "OUT_4") (pintype "output"))
    )
    (net (code "22") (name "/OUT5") (class "Default")
      (node (ref "U9") (pin "4") (pinfunction "OUT_4") (pintype "output"))
    )
    (net (code "23") (name "/OUT6") (class "Default")
      (node (ref "U10") (pin "4") (pinfunction "OUT_4") (pintype "output"))
    )
    (net (code "24") (name "/OUT7") (class "Default")
      (node (ref "U11") (pin "4") (pinfunction "OUT_4") (pintype "output"))
    )
    (net (code "25") (name "/OUT8") (class "Default")
      (node (ref "U12") (pin "4") (pinfunction "OUT_4") (pintype "output"))
    )
    (net (code "26") (name "/SCL") (class "Default")
      (node (ref "U13") (pin "22") (pinfunction "SCL_22") (pintype "input"))
    )
    (net (code "27") (name "/SDA") (class "Default")
      (node (ref "U13") (pin "23") (pinfunction "SDA_23") (pintype "bidirectional"))
    )
    (net (code "28") (name "GND") (class "Default")
      (node (ref "C10") (pin "1") (pinfunction "1_1") (pintype "passive"))
      (node (ref "C11") (pin "1") (pinfunction "1_1") (pintype "passive"))
      (node (ref "C12") (pin "1") (pinfunction "1_1") (pintype "passive"))
      (node (ref "C13") (pin "1") (pinfunction "1_1") (pintype "passive"))
      (node (ref "C14") (pin "1") (pinfunction "1_1") (pintype "passive"))
      (node (ref "C15") (pin "2") (pinfunction "2_2") (pintype "passive"))
      (node (ref "C7") (pin "1") (pinfunction "1_1") (pintype "passive"))
      (node (ref "C8") (pin "1") (pinfunction "1_1") (pintype "passive"))
      (node (ref "C9") (pin "1") (pinfunction "1_1") (pintype "passive"))
      (node (ref "J1") (pin "2") (pinfunction "2_2") (pintype "passive"))
      (node (ref "P3") (pin "2") (pinfunction "-_2") (pintype "power_in"))
      (node (ref "P4") (pin "2") (pinfunction "-_2") (pintype "power_in"))
      (node (ref "P5") (pin "2") (pinfunction "-_2") (pintype "power_in"))
      (node (ref "P6") (pin "2") (pinfunction "-_2") (pintype "power_in"))
      (node (ref "P7") (pin "2") (pinfunction "-_2") (pintype "power_in"))
      (node (ref "P8") (pin "2") (pinfunction "-_2") (pintype "power_in"))
      (node (ref "P9") (pin "2") (pinfunction "-_2") (pintype "power_in"))
      (node (ref "U10") (pin "2") (pinfunction "GND_2") (pintype "power_in"))
      (node (ref "U10") (pin "7") (pinfunction "REF_7") (pintype "input"))
      (node (ref "U11") (pin "2") (pinfunction "GND_2") (pintype "power_in"))
      (node (ref "U11") (pin "7") (pinfunction "REF_7") (pintype "input"))
      (node (ref "U12") (pin "2") (pinfunction "GND_2") (pintype "power_in"))
      (node (ref "U12") (pin "7") (pinfunction "REF_7") (pintype "input"))
      (node (ref "U13") (pin "12") (pinfunction "GND_12") (pintype "power_in"))
      (node (ref "U13") (pin "2") (pinfunction "A1_2") (pintype "input"))
      (node (ref "U13") (pin "21") (pinfunction "A0_21") (pintype "input"))
      (node (ref "U13") (pin "3") (pinfunction "A2_3") (pintype "input"))
      (node (ref "U5") (pin "2") (pinfunction "GND_2") (pintype "power_in"))
      (node (ref "U5") (pin "7") (pinfunction "REF_7") (pintype "input"))
      (node (ref "U6") (pin "2") (pinfunction "GND_2") (pintype "power_in"))
      (node (ref "U6") (pin "7") (pinfunction "REF_7") (pintype "input"))
      (node (ref "U7") (pin "2") (pinfunction "GND_2") (pintype "power_in"))
      (node (ref "U7") (pin "7") (pinfunction "REF_7") (pintype "input"))
      (node (ref "U8") (pin "2") (pinfunction "GND_2") (pintype "power_in"))
      (node (ref "U8") (pin "7") (pinfunction "REF_7") (pintype "input"))
      (node (ref "U9") (pin "2") (pinfunction "GND_2") (pintype "power_in"))
      (node (ref "U9") (pin "7") (pinfunction "REF_7") (pintype "input"))
    )
    (net (code "29") (name "Net-(D3-C)") (class "Default")
      (node (ref "D3") (pin "1") (pinfunction "C_1") (pintype "passive"))
      (node (ref "R13") (pin "2") (pinfunction "2_2") (pintype "passive"))
    )
    (net (code "30") (name "Net-(D4-C)") (class "Default")
      (node (ref "D4") (pin "1") (pinfunction "C_1") (pintype "passive"))
      (node (ref "R14") (pin "2") (pinfunction "2_2") (pintype "passive"))
    )
    (net (code "31") (name "Net-(D5-C)") (class "Default")
      (node (ref "D5") (pin "1") (pinfunction "C_1") (pintype "passive"))
      (node (ref "R15") (pin "2") (pinfunction "2_2") (pintype "passive"))
    )
    (net (code "32") (name "Net-(D6-C)") (class "Default")
      (node (ref "D6") (pin "1") (pinfunction "C_1") (pintype "passive"))
      (node (ref "R16") (pin "2") (pinfunction "2_2") (pintype "passive"))
    )
    (net (code "33") (name "Net-(D7-C)") (class "Default")
      (node (ref "D7") (pin "1") (pinfunction "C_1") (pintype "passive"))
      (node (ref "R17") (pin "2") (pinfunction "2_2") (pintype "passive"))
    )
    (net (code "34") (name "Net-(D8-C)") (class "Default")
      (node (ref "D8") (pin "1") (pinfunction "C_1") (pintype "passive"))
      (node (ref "R18") (pin "2") (pinfunction "2_2") (pintype "passive"))
    )
    (net (code "35") (name "Net-(D9-C)") (class "Default")
      (node (ref "D9") (pin "1") (pinfunction "C_1") (pintype "passive"))
      (node (ref "R19") (pin "2") (pinfunction "2_2") (pintype "passive"))
    )
    (net (code "36") (name "Net-(D10-C)") (class "Default")
      (node (ref "D10") (pin "1") (pinfunction "C_1") (pintype "passive"))
      (node (ref "R20") (pin "2") (pinfunction "2_2") (pintype "passive"))
    )
    (net (code "37") (name "Net-(D11-C)") (class "Default")
      (node (ref "D11") (pin "1") (pinfunction "C_1") (pintype "passive"))
      (node (ref "R21") (pin "2") (pinfunction "2_2") (pintype "passive"))
    )
    (net (code "38") (name "Net-(D12-C)") (class "Default")
      (node (ref "D12") (pin "1") (pinfunction "C_1") (pintype "passive"))
      (node (ref "R22") (pin "2") (pinfunction "2_2") (pintype "passive"))
    )
    (net (code "39") (name "Net-(D13-C)") (class "Default")
      (node (ref "D13") (pin "1") (pinfunction "C_1") (pintype "passive"))
      (node (ref "R23") (pin "2") (pinfunction "2_2") (pintype "passive"))
    )
    (net (code "40") (name "Net-(D14-C)") (class "Default")
      (node (ref "D14") (pin "1") (pinfunction "C_1") (pintype "passive"))
      (node (ref "R24") (pin "2") (pinfunction "2_2") (pintype "passive"))
    )
    (net (code "41") (name "Net-(D15-C)") (class "Default")
      (node (ref "D15") (pin "1") (pinfunction "C_1") (pintype "passive"))
      (node (ref "R25") (pin "2") (pinfunction "2_2") (pintype "passive"))
    )
    (net (code "42") (name "Net-(D16-C)") (class "Default")
      (node (ref "D16") (pin "1") (pinfunction "C_1") (pintype "passive"))
      (node (ref "R26") (pin "2") (pinfunction "2_2") (pintype "passive"))
    )
    (net (code "43") (name "Net-(D17-C)") (class "Default")
      (node (ref "D17") (pin "1") (pinfunction "C_1") (pintype "passive"))
      (node (ref "R27") (pin "2") (pinfunction "2_2") (pintype "passive"))
    )
    (net (code "44") (name "Net-(D18-C)") (class "Default")
      (node (ref "D18") (pin "1") (pinfunction "C_1") (pintype "passive"))
      (node (ref "R28") (pin "2") (pinfunction "2_2") (pintype "passive"))
    )
    (net (code "45") (name "Net-(P3-+)") (class "Default")
      (node (ref "P3") (pin "1") (pinfunction "+_1") (pintype "power_in"))
      (node (ref "R5") (pin "1") (pinfunction "1_1") (pintype "passive"))
      (node (ref "U5") (pin "8") (pinfunction "IN-_8") (pintype "tri_state"))
    )
    (net (code "46") (name "Net-(P4-+)") (class "Default")
      (node (ref "P4") (pin "1") (pinfunction "+_1") (pintype "power_in"))
      (node (ref "R6") (pin "1") (pinfunction "1_1") (pintype "passive"))
      (node (ref "U6") (pin "8") (pinfunction "IN-_8") (pintype "tri_state"))
    )
    (net (code "47") (name "Net-(P5-+)") (class "Default")
      (node (ref "P5") (pin "1") (pinfunction "+_1") (pintype "power_in"))
      (node (ref "R7") (pin "1") (pinfunction "1_1") (pintype "passive"))
      (node (ref "U7") (pin "8") (pinfunction "IN-_8") (pintype "tri_state"))
    )
    (net (code "48") (name "Net-(P6-+)") (class "Default")
      (node (ref "P6") (pin "1") (pinfunction "+_1") (pintype "power_in"))
      (node (ref "R8") (pin "1") (pinfunction "1_1") (pintype "passive"))
      (node (ref "U8") (pin "8") (pinfunction "IN-_8") (pintype "tri_state"))
    )
    (net (code "49") (name "Net-(P7-+)") (class "Default")
      (node (ref "P7") (pin "1") (pinfunction "+_1") (pintype "power_in"))
      (node (ref "R9") (pin "1") (pinfunction "1_1") (pintype "passive"))
      (node (ref "U9") (pin "8") (pinfunction "IN-_8") (pintype "tri_state"))
    )
    (net (code "50") (name "Net-(P8-+)") (class "Default")
      (node (ref "P8") (pin "1") (pinfunction "+_1") (pintype "power_in"))
      (node (ref "R10") (pin "1") (pinfunction "1_1") (pintype "passive"))
      (node (ref "U10") (pin "8") (pinfunction "IN-_8") (pintype "tri_state"))
    )
    (net (code "51") (name "Net-(P9-+)") (class "Default")
      (node (ref "P9") (pin "1") (pinfunction "+_1") (pintype "power_in"))
      (node (ref "R11") (pin "1") (pinfunction "1_1") (pintype "passive"))
      (node (ref "U11") (pin "8") (pinfunction "IN-_8") (pintype "tri_state"))
    )
    (net (code "52") (name "Net-(U12-IN-)") (class "Default")
      (node (ref "J1") (pin "1") (pinfunction "1_1") (pintype "passive"))
      (node (ref "R12") (pin "1") (pinfunction "1_1") (pintype "passive"))
      (node (ref "U12") (pin "8") (pinfunction "IN-_8") (pintype "tri_state"))
    )
    (net (code "53") (name "VCC") (class "Default")
      (node (ref "R10") (pin "2") (pinfunction "2_2") (pintype "passive"))
      (node (ref "R11") (pin "2") (pinfunction "2_2") (pintype "passive"))
      (node (ref "R12") (pin "2") (pinfunction "2_2") (pintype "passive"))
      (node (ref "R5") (pin "2") (pinfunction "2_2") (pintype "passive"))
      (node (ref "R6") (pin "2") (pinfunction "2_2") (pintype "passive"))
      (node (ref "R7") (pin "2") (pinfunction "2_2") (pintype "passive"))
      (node (ref "R8") (pin "2") (pinfunction "2_2") (pintype "passive"))
      (node (ref "R9") (pin "2") (pinfunction "2_2") (pintype "passive"))
      (node (ref "U10") (pin "1") (pinfunction "IN+_1") (pintype "tri_state"))
      (node (ref "U11") (pin "1") (pinfunction "IN+_1") (pintype "tri_state"))
      (node (ref "U12") (pin "1") (pinfunction "IN+_1") (pintype "tri_state"))
      (node (ref "U5") (pin "1") (pinfunction "IN+_1") (pintype "tri_state"))
      (node (ref "U6") (pin "1") (pinfunction "IN+_1") (pintype "tri_state"))
      (node (ref "U7") (pin "1") (pinfunction "IN+_1") (pintype "tri_state"))
      (node (ref "U8") (pin "1") (pinfunction "IN+_1") (pintype "tri_state"))
      (node (ref "U9") (pin "1") (pinfunction "IN+_1") (pintype "tri_state"))
    )
    (net (code "54") (name "unconnected-(U13-~{INT}-Pad1)") (class "Default")
      (node (ref "U13") (pin "1") (pinfunction "~{INT}_1") (pintype "output"))
    )
  )
)
